# 2-RJ45.net
KiCad netlist of a schematic drawn in Altium Designer
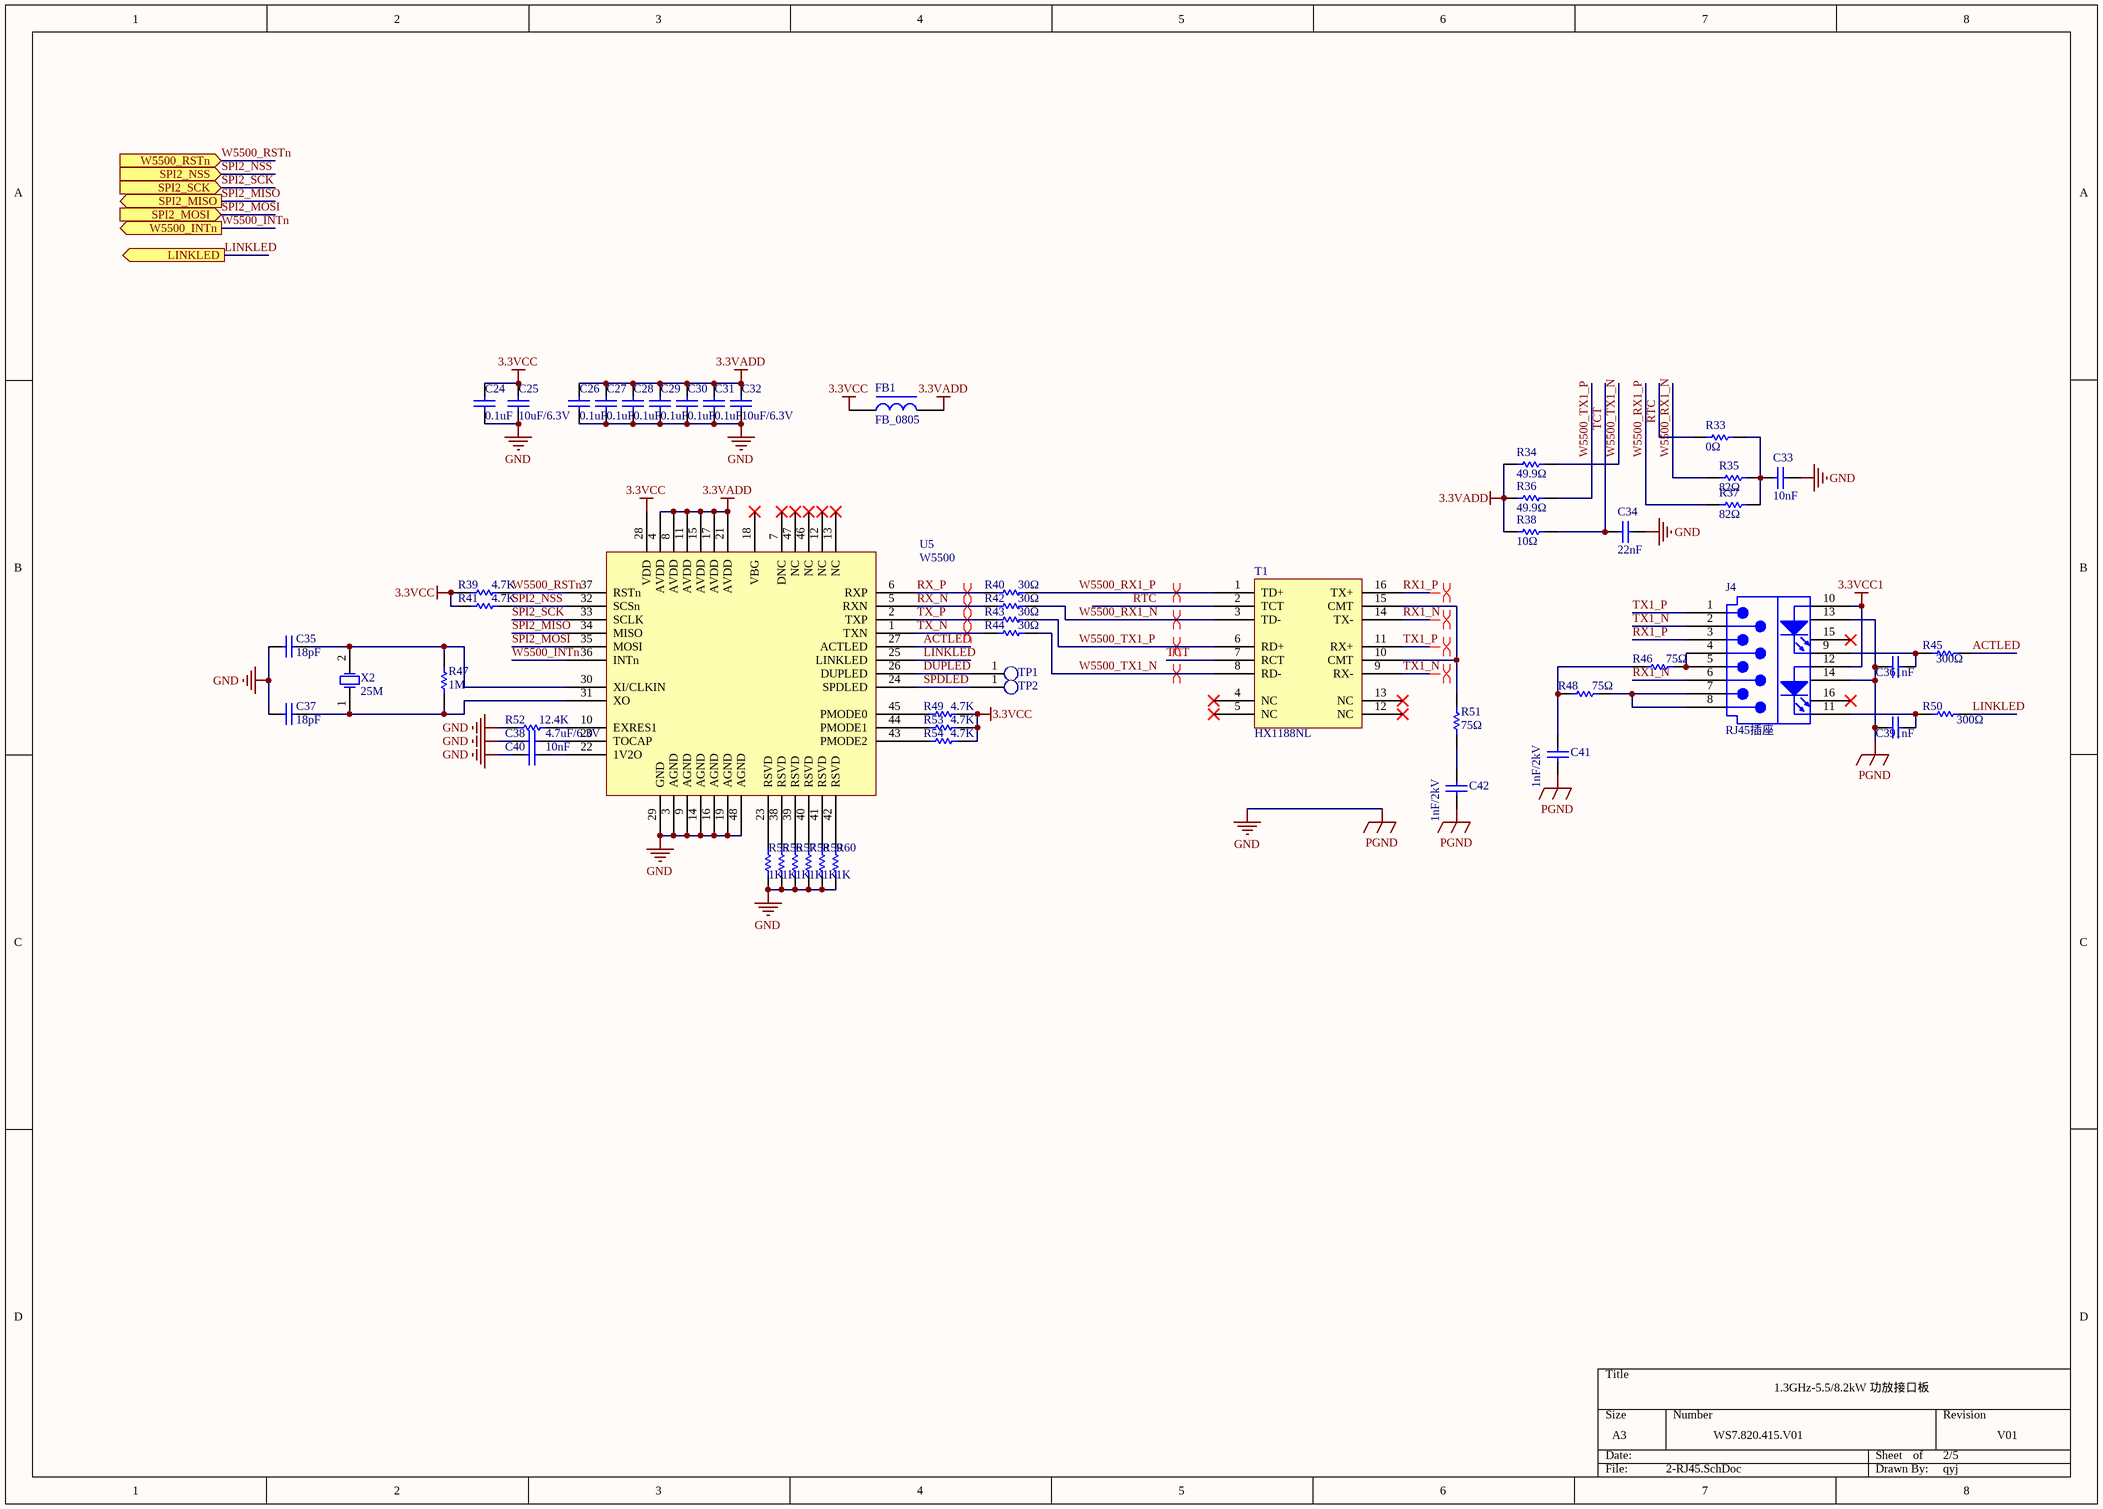
[diagram p0: 2-RJ45.SchDoc]

(export (version "E")
  (design (tool "Eeschema 10.0.6"))
  (components
    (comp (ref "C24")
      (value "0.1uF")
      (footprint "C0603")
      (description "贴片电容_GRM188R71H104KA01D_0.1uF±10%,50V,0603")
      (libsource (lib "20贴片电容0603") (part "0.1uF贴片电容"))
    )
    (comp (ref "C25")
      (value "10uF/6.3V")
      (footprint "C0603")
      (description "贴片电容_GRM188R60J106ME47D_10uF±20%,6.3V,0603")
      (libsource (lib "20贴片电容0603") (part "10uF贴片电容"))
    )
    (comp (ref "C26")
      (value "0.1uF")
      (footprint "C0603")
      (description "贴片电容_GRM188R71H104KA01D_0.1uF±10%,50V,0603")
      (libsource (lib "20贴片电容0603") (part "0.1uF贴片电容"))
    )
    (comp (ref "C27")
      (value "0.1uF")
      (footprint "C0603")
      (description "贴片电容_GRM188R71H104KA01D_0.1uF±10%,50V,0603")
      (libsource (lib "20贴片电容0603") (part "0.1uF贴片电容"))
    )
    (comp (ref "C28")
      (value "0.1uF")
      (footprint "C0603")
      (description "贴片电容_GRM188R71H104KA01D_0.1uF±10%,50V,0603")
      (libsource (lib "20贴片电容0603") (part "0.1uF贴片电容"))
    )
    (comp (ref "C29")
      (value "0.1uF")
      (footprint "C0603")
      (description "贴片电容_GRM188R71H104KA01D_0.1uF±10%,50V,0603")
      (libsource (lib "20贴片电容0603") (part "0.1uF贴片电容"))
    )
    (comp (ref "C30")
      (value "0.1uF")
      (footprint "C0603")
      (description "贴片电容_GRM188R71H104KA01D_0.1uF±10%,50V,0603")
      (libsource (lib "20贴片电容0603") (part "0.1uF贴片电容"))
    )
    (comp (ref "C31")
      (value "0.1uF")
      (footprint "C0603")
      (description "贴片电容_GRM188R71H104KA01D_0.1uF±10%,50V,0603")
      (libsource (lib "20贴片电容0603") (part "0.1uF贴片电容"))
    )
    (comp (ref "C32")
      (value "10uF/6.3V")
      (footprint "C0603")
      (description "贴片电容_GRM188R60J106ME47D_10uF±20%,6.3V,0603")
      (libsource (lib "20贴片电容0603") (part "10uF贴片电容"))
    )
    (comp (ref "C33")
      (value "10nF")
      (footprint "C0603")
      (description "C0603C103K5RAC_10nF±10%,50V,0603")
      (fields (field (name "MPN") "KEMET"))
      (libsource (lib "20贴片电容0603") (part "0.1uF贴片电容"))
    )
    (comp (ref "C34")
      (value "22nF")
      (footprint "C0603")
      (description "贴片电容_22nF±5%,50V,0603")
      (libsource (lib "20贴片电容0603") (part "27nF贴片电容"))
    )
    (comp (ref "C35")
      (value "18pF")
      (footprint "C0603")
      (description "贴片电容_GRM1885C1H180JA01D_18pF±5%,50V,0603")
      (libsource (lib "20贴片电容0603") (part "18pF贴片电容"))
    )
    (comp (ref "C36")
      (value "1nF")
      (footprint "C0603")
      (description "贴片电容_GRM188R71H102KA01_1000pF±10%,50V,0603")
      (libsource (lib "20贴片电容0603") (part "1000pF贴片电容"))
    )
    (comp (ref "C37")
      (value "18pF")
      (footprint "C0603")
      (description "贴片电容_GRM1885C1H180JA01D_18pF±5%,50V,0603")
      (libsource (lib "20贴片电容0603") (part "18pF贴片电容"))
    )
    (comp (ref "C38")
      (value "4.7uF/6.3V")
      (footprint "C0603")
      (description "GRM188R61C475K_4.7uF±10%,16V,0603")
      (fields (field (name "MPN") "Murata"))
      (libsource (lib "20贴片电容0603") (part "1uF贴片电容"))
    )
    (comp (ref "C39")
      (value "1nF")
      (footprint "C0603")
      (description "贴片电容_GRM188R71H102KA01_1000pF±10%,50V,0603")
      (libsource (lib "20贴片电容0603") (part "1000pF贴片电容"))
    )
    (comp (ref "C40")
      (value "10nF")
      (footprint "C0603")
      (description "C0603C103K5RAC_10nF±10%,50V,0603")
      (fields (field (name "MPN") "KEMET"))
      (libsource (lib "20贴片电容0603") (part "0.1uF贴片电容"))
    )
    (comp (ref "C41")
      (value "1nF/2kV")
      (footprint "C1206")
      (description "贴片电容_C1206C102J5GAC _1000pF±5%,50V,1206")
      (fields (field (name "MPN") "KEMET"))
      (libsource (lib "22贴片电容1210") (part "10uF贴片电容"))
    )
    (comp (ref "C42")
      (value "1nF/2kV")
      (footprint "C1206")
      (description "贴片电容_C1206C102J5GAC _1000pF±5%,50V,1206")
      (fields (field (name "MPN") "KEMET"))
      (libsource (lib "22贴片电容1210") (part "10uF贴片电容"))
    )
    (comp (ref "FB1")
      (value "FB_0805")
      (footprint "L0805")
      (description "贴片磁珠_600R,0805")
      (libsource (lib "32贴片磁珠0805") (part "0805贴片磁珠"))
    )
    (comp (ref "J4")
      (value "RJ45插座")
      (footprint "RJ45TH-1x1-2R54-LED")
      (description "RJ45插座_1*1,带左黄右绿灯,弯脚")
      (fields (field (name "MPN") "朱迅"))
      (libsource (lib "91连接器") (part "RJ45弯脚带灯"))
    )
    (comp (ref "R33")
      (value "0Ω")
      (footprint "R0603")
      (description "贴片电阻_0Ω±5%,0603")
      (libsource (lib "10贴片电阻0603") (part "0Ω贴片电阻"))
    )
    (comp (ref "R34")
      (value "49.9Ω")
      (footprint "R0603")
      (description "贴片电阻_49.9Ω±1%,0603")
      (libsource (lib "10贴片电阻0603") (part "51Ω贴片电阻"))
    )
    (comp (ref "R35")
      (value "82Ω")
      (footprint "R0603")
      (description "贴片电阻_82Ω±1%,0603")
      (libsource (lib "10贴片电阻0603") (part "51Ω贴片电阻"))
    )
    (comp (ref "R36")
      (value "49.9Ω")
      (footprint "R0603")
      (description "贴片电阻_49.9Ω±1%,0603")
      (libsource (lib "10贴片电阻0603") (part "51Ω贴片电阻"))
    )
    (comp (ref "R37")
      (value "82Ω")
      (footprint "R0603")
      (description "贴片电阻_82Ω±1%,0603")
      (libsource (lib "10贴片电阻0603") (part "51Ω贴片电阻"))
    )
    (comp (ref "R38")
      (value "10Ω")
      (footprint "R0603")
      (description "贴片电阻_10Ω±5%,0603")
      (libsource (lib "10贴片电阻0603") (part "10Ω贴片电阻"))
    )
    (comp (ref "R39")
      (value "4.7K")
      (footprint "R0603")
      (description "贴片电阻_4.7K±5%,0603")
      (libsource (lib "10贴片电阻0603") (part "4.7K贴片电阻"))
    )
    (comp (ref "R40")
      (value "30Ω")
      (footprint "R0603")
      (description "贴片电阻_30Ω±5%,0603")
      (libsource (lib "10贴片电阻0603") (part "30Ω贴片电阻"))
    )
    (comp (ref "R41")
      (value "4.7K")
      (footprint "R0603")
      (description "贴片电阻_4.7K±5%,0603")
      (libsource (lib "10贴片电阻0603") (part "4.7K贴片电阻"))
    )
    (comp (ref "R42")
      (value "30Ω")
      (footprint "R0603")
      (description "贴片电阻_30Ω±5%,0603")
      (libsource (lib "10贴片电阻0603") (part "30Ω贴片电阻"))
    )
    (comp (ref "R43")
      (value "30Ω")
      (footprint "R0603")
      (description "贴片电阻_30Ω±5%,0603")
      (libsource (lib "10贴片电阻0603") (part "30Ω贴片电阻"))
    )
    (comp (ref "R44")
      (value "30Ω")
      (footprint "R0603")
      (description "贴片电阻_30Ω±5%,0603")
      (libsource (lib "10贴片电阻0603") (part "30Ω贴片电阻"))
    )
    (comp (ref "R45")
      (value "300Ω")
      (footprint "R0603")
      (description "贴片电阻_300Ω±5%,0603")
      (libsource (lib "10贴片电阻0603") (part "300Ω贴片电阻"))
    )
    (comp (ref "R46")
      (value "75Ω")
      (footprint "R0805")
      (description "贴片电阻_75Ω±5%,0805")
      (libsource (lib "11贴片电阻0805") (part "75Ω贴片电阻"))
    )
    (comp (ref "R47")
      (value "1M")
      (footprint "R0603")
      (description "贴片电阻_1M±5%,0603")
      (libsource (lib "10贴片电阻0603") (part "1M贴片电阻"))
    )
    (comp (ref "R48")
      (value "75Ω")
      (footprint "R0805")
      (description "贴片电阻_75Ω±5%,0805")
      (libsource (lib "11贴片电阻0805") (part "75Ω贴片电阻"))
    )
    (comp (ref "R49")
      (value "4.7K")
      (footprint "R0603")
      (description "贴片电阻_4.7K±5%,0603")
      (libsource (lib "10贴片电阻0603") (part "4.7K贴片电阻"))
    )
    (comp (ref "R50")
      (value "300Ω")
      (footprint "R0603")
      (description "贴片电阻_300Ω±5%,0603")
      (libsource (lib "10贴片电阻0603") (part "300Ω贴片电阻"))
    )
    (comp (ref "R51")
      (value "75Ω")
      (footprint "R1206")
      (description "贴片电阻_75Ω±5%,1206")
      (libsource (lib "11贴片电阻0805") (part "75Ω贴片电阻"))
    )
    (comp (ref "R52")
      (value "12.4K")
      (footprint "R0603")
      (description "贴片电阻_12.4K±1%,0603")
      (libsource (lib "10贴片电阻0603") (part "12K贴片电阻"))
    )
    (comp (ref "R53")
      (value "4.7K")
      (footprint "R0603")
      (description "贴片电阻_4.7K±5%,0603")
      (libsource (lib "10贴片电阻0603") (part "4.7K贴片电阻"))
    )
    (comp (ref "R54")
      (value "4.7K")
      (footprint "R0603")
      (description "贴片电阻_4.7K±5%,0603")
      (libsource (lib "10贴片电阻0603") (part "4.7K贴片电阻"))
    )
    (comp (ref "R55")
      (value "1K")
      (footprint "R0603")
      (description "贴片电阻_1K±5%,0603")
      (libsource (lib "10贴片电阻0603") (part "1K贴片电阻"))
    )
    (comp (ref "R56")
      (value "1K")
      (footprint "R0603")
      (description "贴片电阻_1K±5%,0603")
      (libsource (lib "10贴片电阻0603") (part "1K贴片电阻"))
    )
    (comp (ref "R57")
      (value "1K")
      (footprint "R0603")
      (description "贴片电阻_1K±5%,0603")
      (libsource (lib "10贴片电阻0603") (part "1K贴片电阻"))
    )
    (comp (ref "R58")
      (value "1K")
      (footprint "R0603")
      (description "贴片电阻_1K±5%,0603")
      (libsource (lib "10贴片电阻0603") (part "1K贴片电阻"))
    )
    (comp (ref "R59")
      (value "1K")
      (footprint "R0603")
      (description "贴片电阻_1K±5%,0603")
      (libsource (lib "10贴片电阻0603") (part "1K贴片电阻"))
    )
    (comp (ref "R60")
      (value "1K")
      (footprint "R0603")
      (description "贴片电阻_1K±5%,0603")
      (libsource (lib "10贴片电阻0603") (part "1K贴片电阻"))
    )
    (comp (ref "T1")
      (value "HX1188NL")
      (footprint "SOP16-1R27-7R11x12R7")
      (description "网络变压器_HX1188NL_百兆,SOIC16")
      (libsource (lib "89网络变压器") (part "HX1188NL"))
    )
    (comp (ref "TP1")
      (value "TEST")
      (footprint "TP0R8")
      (description "表贴测试点0.8mm")
      (libsource (lib "103其他（hole，test等）") (part "TP0.8mm"))
    )
    (comp (ref "TP2")
      (value "TEST")
      (footprint "TP0R8")
      (description "表贴测试点0.8mm")
      (libsource (lib "103其他（hole，test等）") (part "TP0.8mm"))
    )
    (comp (ref "U5")
      (value "W5500")
      (footprint "TQFN48-0R5-7X7")
      (description "以太网控制器_W5500_LQFP48")
      (libsource (lib "86网口芯片") (part "W5500"))
    )
    (comp (ref "X2")
      (value "25M")
      (footprint "CRY2SM-6R0x3R5")
      (description "贴片无源晶体_25MHz,30ppm,6035封装")
      (libsource (lib "60振荡器") (part "25M贴片无源晶体"))
    )
  )
  (nets
    (net (code "1") (name "/ACTLED") (class "Default")
      (node (ref "R45") (pin "2") (pinfunction "2_2") (pintype "passive"))
      (node (ref "U5") (pin "27") (pinfunction "ACTLED_27") (pintype "passive"))
    )
    (net (code "2") (name "/DUPLED") (class "Default")
      (node (ref "TP1") (pin "1") (pinfunction "TP_1") (pintype "passive"))
      (node (ref "U5") (pin "26") (pinfunction "DUPLED_26") (pintype "passive"))
    )
    (net (code "3") (name "/LINKLED") (class "Default")
      (node (ref "R50") (pin "2") (pinfunction "2_2") (pintype "passive"))
      (node (ref "U5") (pin "25") (pinfunction "LINKLED_25") (pintype "passive"))
    )
    (net (code "4") (name "/RTC") (class "Default")
      (node (ref "R33") (pin "2") (pinfunction "2_2") (pintype "passive"))
      (node (ref "T1") (pin "2") (pinfunction "TCT_2") (pintype "passive"))
    )
    (net (code "5") (name "/RX1_N") (class "Default")
      (node (ref "J4") (pin "6") (pinfunction "RX-_6") (pintype "passive"))
      (node (ref "T1") (pin "14") (pinfunction "TX-_14") (pintype "passive"))
    )
    (net (code "6") (name "/RX1_P") (class "Default")
      (node (ref "J4") (pin "3") (pinfunction "RX+_3") (pintype "passive"))
      (node (ref "T1") (pin "16") (pinfunction "TX+_16") (pintype "passive"))
    )
    (net (code "7") (name "/RX_N") (class "Default")
      (node (ref "R42") (pin "1") (pinfunction "1_1") (pintype "passive"))
      (node (ref "U5") (pin "5") (pinfunction "RXN_5") (pintype "passive"))
    )
    (net (code "8") (name "/RX_P") (class "Default")
      (node (ref "R40") (pin "1") (pinfunction "1_1") (pintype "passive"))
      (node (ref "U5") (pin "6") (pinfunction "RXP_6") (pintype "passive"))
    )
    (net (code "9") (name "/SPDLED") (class "Default")
      (node (ref "TP2") (pin "1") (pinfunction "TP_1") (pintype "passive"))
      (node (ref "U5") (pin "24") (pinfunction "SPDLED_24") (pintype "passive"))
    )
    (net (code "10") (name "/SPI2_MISO") (class "Default")
      (node (ref "U5") (pin "34") (pinfunction "MISO_34") (pintype "passive"))
    )
    (net (code "11") (name "/SPI2_MOSI") (class "Default")
      (node (ref "U5") (pin "35") (pinfunction "MOSI_35") (pintype "passive"))
    )
    (net (code "12") (name "/SPI2_NSS") (class "Default")
      (node (ref "R41") (pin "1") (pinfunction "1_1") (pintype "passive"))
      (node (ref "U5") (pin "32") (pinfunction "SCSn_32") (pintype "passive"))
    )
    (net (code "13") (name "/SPI2_SCK") (class "Default")
      (node (ref "U5") (pin "33") (pinfunction "SCLK_33") (pintype "passive"))
    )
    (net (code "14") (name "/TCT") (class "Default")
      (node (ref "C34") (pin "2") (pinfunction "2_2") (pintype "passive"))
      (node (ref "R38") (pin "1") (pinfunction "1_1") (pintype "passive"))
      (node (ref "T1") (pin "7") (pinfunction "RCT_7") (pintype "passive"))
    )
    (net (code "15") (name "/TX1_N") (class "Default")
      (node (ref "J4") (pin "2") (pinfunction "TX-_2") (pintype "passive"))
      (node (ref "T1") (pin "9") (pinfunction "RX-_9") (pintype "passive"))
    )
    (net (code "16") (name "/TX1_P") (class "Default")
      (node (ref "J4") (pin "1") (pinfunction "TX+_1") (pintype "passive"))
      (node (ref "T1") (pin "11") (pinfunction "RX+_11") (pintype "passive"))
    )
    (net (code "17") (name "/TX_N") (class "Default")
      (node (ref "R44") (pin "1") (pinfunction "1_1") (pintype "passive"))
      (node (ref "U5") (pin "1") (pinfunction "TXN_1") (pintype "passive"))
    )
    (net (code "18") (name "/TX_P") (class "Default")
      (node (ref "R43") (pin "1") (pinfunction "1_1") (pintype "passive"))
      (node (ref "U5") (pin "2") (pinfunction "TXP_2") (pintype "passive"))
    )
    (net (code "19") (name "/W5500_INTn") (class "Default")
      (node (ref "U5") (pin "36") (pinfunction "INTn_36") (pintype "passive"))
    )
    (net (code "20") (name "/W5500_RSTn") (class "Default")
      (node (ref "R39") (pin "1") (pinfunction "1_1") (pintype "passive"))
      (node (ref "U5") (pin "37") (pinfunction "RSTn_37") (pintype "passive"))
    )
    (net (code "21") (name "/W5500_RX1_N") (class "Default")
      (node (ref "R35") (pin "2") (pinfunction "2_2") (pintype "passive"))
      (node (ref "R42") (pin "2") (pinfunction "2_2") (pintype "passive"))
      (node (ref "T1") (pin "3") (pinfunction "TD-_3") (pintype "passive"))
    )
    (net (code "22") (name "/W5500_RX1_P") (class "Default")
      (node (ref "R37") (pin "2") (pinfunction "2_2") (pintype "passive"))
      (node (ref "R40") (pin "2") (pinfunction "2_2") (pintype "passive"))
      (node (ref "T1") (pin "1") (pinfunction "TD+_1") (pintype "passive"))
    )
    (net (code "23") (name "/W5500_TX1_N") (class "Default")
      (node (ref "R34") (pin "1") (pinfunction "1_1") (pintype "passive"))
      (node (ref "R44") (pin "2") (pinfunction "2_2") (pintype "passive"))
      (node (ref "T1") (pin "8") (pinfunction "RD-_8") (pintype "passive"))
    )
    (net (code "24") (name "/W5500_TX1_P") (class "Default")
      (node (ref "R36") (pin "1") (pinfunction "1_1") (pintype "passive"))
      (node (ref "R43") (pin "2") (pinfunction "2_2") (pintype "passive"))
      (node (ref "T1") (pin "6") (pinfunction "RD+_6") (pintype "passive"))
    )
    (net (code "25") (name "3.3VADD") (class "Default")
      (node (ref "C26") (pin "2") (pinfunction "2_2") (pintype "passive"))
      (node (ref "C27") (pin "2") (pinfunction "2_2") (pintype "passive"))
      (node (ref "C28") (pin "2") (pinfunction "2_2") (pintype "passive"))
      (node (ref "C29") (pin "2") (pinfunction "2_2") (pintype "passive"))
      (node (ref "C30") (pin "2") (pinfunction "2_2") (pintype "passive"))
      (node (ref "C31") (pin "2") (pinfunction "2_2") (pintype "passive"))
      (node (ref "C32") (pin "2") (pinfunction "2_2") (pintype "passive"))
      (node (ref "FB1") (pin "2") (pinfunction "2_2") (pintype "passive"))
      (node (ref "R34") (pin "2") (pinfunction "2_2") (pintype "passive"))
      (node (ref "R36") (pin "2") (pinfunction "2_2") (pintype "passive"))
      (node (ref "R38") (pin "2") (pinfunction "2_2") (pintype "passive"))
      (node (ref "U5") (pin "11") (pinfunction "AVDD_11") (pintype "passive"))
      (node (ref "U5") (pin "15") (pinfunction "AVDD_15") (pintype "passive"))
      (node (ref "U5") (pin "17") (pinfunction "AVDD_17") (pintype "passive"))
      (node (ref "U5") (pin "21") (pinfunction "AVDD_21") (pintype "passive"))
      (node (ref "U5") (pin "4") (pinfunction "AVDD_4") (pintype "passive"))
      (node (ref "U5") (pin "8") (pinfunction "AVDD_8") (pintype "passive"))
    )
    (net (code "26") (name "3.3VCC") (class "Default")
      (node (ref "C24") (pin "2") (pinfunction "2_2") (pintype "passive"))
      (node (ref "C25") (pin "2") (pinfunction "2_2") (pintype "passive"))
      (node (ref "FB1") (pin "1") (pinfunction "1_1") (pintype "passive"))
      (node (ref "R39") (pin "2") (pinfunction "2_2") (pintype "passive"))
      (node (ref "R41") (pin "2") (pinfunction "2_2") (pintype "passive"))
      (node (ref "R49") (pin "2") (pinfunction "2_2") (pintype "passive"))
      (node (ref "R53") (pin "2") (pinfunction "2_2") (pintype "passive"))
      (node (ref "R54") (pin "2") (pinfunction "2_2") (pintype "passive"))
      (node (ref "U5") (pin "28") (pinfunction "VDD_28") (pintype "passive"))
    )
    (net (code "27") (name "3.3VCC1") (class "Default")
      (node (ref "J4") (pin "10") (pinfunction "A1_10") (pintype "passive"))
      (node (ref "J4") (pin "12") (pinfunction "A2_12") (pintype "passive"))
    )
    (net (code "28") (name "GND") (class "Default")
      (node (ref "C24") (pin "1") (pinfunction "1_1") (pintype "passive"))
      (node (ref "C25") (pin "1") (pinfunction "1_1") (pintype "passive"))
      (node (ref "C26") (pin "1") (pinfunction "1_1") (pintype "passive"))
      (node (ref "C27") (pin "1") (pinfunction "1_1") (pintype "passive"))
      (node (ref "C28") (pin "1") (pinfunction "1_1") (pintype "passive"))
      (node (ref "C29") (pin "1") (pinfunction "1_1") (pintype "passive"))
      (node (ref "C30") (pin "1") (pinfunction "1_1") (pintype "passive"))
      (node (ref "C31") (pin "1") (pinfunction "1_1") (pintype "passive"))
      (node (ref "C32") (pin "1") (pinfunction "1_1") (pintype "passive"))
      (node (ref "C33") (pin "1") (pinfunction "1_1") (pintype "passive"))
      (node (ref "C34") (pin "1") (pinfunction "1_1") (pintype "passive"))
      (node (ref "C35") (pin "1") (pinfunction "1_1") (pintype "passive"))
      (node (ref "C36") (pin "1") (pinfunction "1_1") (pintype "passive"))
      (node (ref "C37") (pin "1") (pinfunction "1_1") (pintype "passive"))
      (node (ref "C38") (pin "1") (pinfunction "1_1") (pintype "passive"))
      (node (ref "C39") (pin "1") (pinfunction "1_1") (pintype "passive"))
      (node (ref "C40") (pin "1") (pinfunction "1_1") (pintype "passive"))
      (node (ref "C41") (pin "1") (pinfunction "1_1") (pintype "passive"))
      (node (ref "C42") (pin "1") (pinfunction "1_1") (pintype "passive"))
      (node (ref "J4") (pin "13") (pinfunction "13_13") (pintype "passive"))
      (node (ref "J4") (pin "14") (pinfunction "14_14") (pintype "passive"))
      (node (ref "R52") (pin "1") (pinfunction "1_1") (pintype "passive"))
      (node (ref "R55") (pin "1") (pinfunction "1_1") (pintype "passive"))
      (node (ref "R56") (pin "1") (pinfunction "1_1") (pintype "passive"))
      (node (ref "R57") (pin "1") (pinfunction "1_1") (pintype "passive"))
      (node (ref "R58") (pin "1") (pinfunction "1_1") (pintype "passive"))
      (node (ref "R59") (pin "1") (pinfunction "1_1") (pintype "passive"))
      (node (ref "R60") (pin "1") (pinfunction "1_1") (pintype "passive"))
      (node (ref "U5") (pin "14") (pinfunction "AGND_14") (pintype "passive"))
      (node (ref "U5") (pin "16") (pinfunction "AGND_16") (pintype "passive"))
      (node (ref "U5") (pin "19") (pinfunction "AGND_19") (pintype "passive"))
      (node (ref "U5") (pin "29") (pinfunction "GND_29") (pintype "passive"))
      (node (ref "U5") (pin "3") (pinfunction "AGND_3") (pintype "passive"))
      (node (ref "U5") (pin "48") (pinfunction "AGND_48") (pintype "passive"))
      (node (ref "U5") (pin "9") (pinfunction "AGND_9") (pintype "passive"))
    )
    (net (code "29") (name "Net-(C33-Pad2)") (class "Default")
      (node (ref "C33") (pin "2") (pinfunction "2_2") (pintype "passive"))
      (node (ref "R33") (pin "1") (pinfunction "1_1") (pintype "passive"))
      (node (ref "R35") (pin "1") (pinfunction "1_1") (pintype "passive"))
      (node (ref "R37") (pin "1") (pinfunction "1_1") (pintype "passive"))
    )
    (net (code "30") (name "Net-(C41-Pad2)") (class "Default")
      (node (ref "C41") (pin "2") (pinfunction "2_2") (pintype "passive"))
      (node (ref "R46") (pin "1") (pinfunction "1_1") (pintype "passive"))
      (node (ref "R48") (pin "1") (pinfunction "1_1") (pintype "passive"))
    )
    (net (code "31") (name "Net-(C42-Pad2)") (class "Default")
      (node (ref "C42") (pin "2") (pinfunction "2_2") (pintype "passive"))
      (node (ref "R51") (pin "1") (pinfunction "1_1") (pintype "passive"))
    )
    (net (code "32") (name "Net-(J4-K1)") (class "Default")
      (node (ref "C36") (pin "2") (pinfunction "2_2") (pintype "passive"))
      (node (ref "J4") (pin "9") (pinfunction "K1_9") (pintype "passive"))
      (node (ref "R45") (pin "1") (pinfunction "1_1") (pintype "passive"))
    )
    (net (code "33") (name "Net-(J4-K2)") (class "Default")
      (node (ref "C39") (pin "2") (pinfunction "2_2") (pintype "passive"))
      (node (ref "J4") (pin "11") (pinfunction "K2_11") (pintype "passive"))
      (node (ref "R50") (pin "1") (pinfunction "1_1") (pintype "passive"))
    )
    (net (code "34") (name "Net-(J4-NC-Pad4)") (class "Default")
      (node (ref "J4") (pin "4") (pinfunction "NC_4") (pintype "passive"))
      (node (ref "J4") (pin "5") (pinfunction "NC_5") (pintype "passive"))
      (node (ref "R46") (pin "2") (pinfunction "2_2") (pintype "passive"))
    )
    (net (code "35") (name "Net-(J4-NC-Pad7)") (class "Default")
      (node (ref "J4") (pin "7") (pinfunction "NC_7") (pintype "passive"))
      (node (ref "J4") (pin "8") (pinfunction "NC_8") (pintype "passive"))
      (node (ref "R48") (pin "2") (pinfunction "2_2") (pintype "passive"))
    )
    (net (code "36") (name "Net-(R51-Pad2)") (class "Default")
      (node (ref "R51") (pin "2") (pinfunction "2_2") (pintype "passive"))
      (node (ref "T1") (pin "10") (pinfunction "CMT_10") (pintype "passive"))
      (node (ref "T1") (pin "15") (pinfunction "CMT_15") (pintype "passive"))
    )
    (net (code "37") (name "Net-(R55-Pad2)") (class "Default")
      (node (ref "R55") (pin "2") (pinfunction "2_2") (pintype "passive"))
      (node (ref "U5") (pin "23") (pinfunction "RSVD_23") (pintype "passive"))
    )
    (net (code "38") (name "Net-(R56-Pad2)") (class "Default")
      (node (ref "R56") (pin "2") (pinfunction "2_2") (pintype "passive"))
      (node (ref "U5") (pin "38") (pinfunction "RSVD_38") (pintype "passive"))
    )
    (net (code "39") (name "Net-(R57-Pad2)") (class "Default")
      (node (ref "R57") (pin "2") (pinfunction "2_2") (pintype "passive"))
      (node (ref "U5") (pin "39") (pinfunction "RSVD_39") (pintype "passive"))
    )
    (net (code "40") (name "Net-(R58-Pad2)") (class "Default")
      (node (ref "R58") (pin "2") (pinfunction "2_2") (pintype "passive"))
      (node (ref "U5") (pin "40") (pinfunction "RSVD_40") (pintype "passive"))
    )
    (net (code "41") (name "Net-(R59-Pad2)") (class "Default")
      (node (ref "R59") (pin "2") (pinfunction "2_2") (pintype "passive"))
      (node (ref "U5") (pin "41") (pinfunction "RSVD_41") (pintype "passive"))
    )
    (net (code "42") (name "Net-(R60-Pad2)") (class "Default")
      (node (ref "R60") (pin "2") (pinfunction "2_2") (pintype "passive"))
      (node (ref "U5") (pin "42") (pinfunction "RSVD_42") (pintype "passive"))
    )
    (net (code "43") (name "Net-(U5-1V2O)") (class "Default")
      (node (ref "C40") (pin "2") (pinfunction "2_2") (pintype "passive"))
      (node (ref "U5") (pin "22") (pinfunction "1V2O_22") (pintype "passive"))
    )
    (net (code "44") (name "Net-(U5-EXRES1)") (class "Default")
      (node (ref "R52") (pin "2") (pinfunction "2_2") (pintype "passive"))
      (node (ref "U5") (pin "10") (pinfunction "EXRES1_10") (pintype "passive"))
    )
    (net (code "45") (name "Net-(U5-PMODE0)") (class "Default")
      (node (ref "R49") (pin "1") (pinfunction "1_1") (pintype "passive"))
      (node (ref "U5") (pin "45") (pinfunction "PMODE0_45") (pintype "passive"))
    )
    (net (code "46") (name "Net-(U5-PMODE1)") (class "Default")
      (node (ref "R53") (pin "1") (pinfunction "1_1") (pintype "passive"))
      (node (ref "U5") (pin "44") (pinfunction "PMODE1_44") (pintype "passive"))
    )
    (net (code "47") (name "Net-(U5-PMODE2)") (class "Default")
      (node (ref "R54") (pin "1") (pinfunction "1_1") (pintype "passive"))
      (node (ref "U5") (pin "43") (pinfunction "PMODE2_43") (pintype "passive"))
    )
    (net (code "48") (name "Net-(U5-TOCAP)") (class "Default")
      (node (ref "C38") (pin "2") (pinfunction "2_2") (pintype "passive"))
      (node (ref "U5") (pin "20") (pinfunction "TOCAP_20") (pintype "passive"))
    )
    (net (code "49") (name "Net-(U5-XI{slash}CLKIN)") (class "Default")
      (node (ref "C35") (pin "2") (pinfunction "2_2") (pintype "passive"))
      (node (ref "R47") (pin "2") (pinfunction "2_2") (pintype "passive"))
      (node (ref "U5") (pin "30") (pinfunction "XI/CLKIN_30") (pintype "passive"))
      (node (ref "X2") (pin "2") (pinfunction "OSC2_2") (pintype "passive"))
    )
    (net (code "50") (name "Net-(U5-XO)") (class "Default")
      (node (ref "C37") (pin "2") (pinfunction "2_2") (pintype "passive"))
      (node (ref "R47") (pin "1") (pinfunction "1_1") (pintype "passive"))
      (node (ref "U5") (pin "31") (pinfunction "XO_31") (pintype "passive"))
      (node (ref "X2") (pin "1") (pinfunction "OSC1_1") (pintype "passive"))
    )
    (net (code "51") (name "unconnected-(J4-Pad15)") (class "Default")
      (node (ref "J4") (pin "15") (pinfunction "15_15") (pintype "passive+no_connect"))
    )
    (net (code "52") (name "unconnected-(J4-Pad16)") (class "Default")
      (node (ref "J4") (pin "16") (pinfunction "16_16") (pintype "passive+no_connect"))
    )
    (net (code "53") (name "unconnected-(T1-NC-Pad4)") (class "Default")
      (node (ref "T1") (pin "4") (pinfunction "NC_4") (pintype "passive+no_connect"))
    )
    (net (code "54") (name "unconnected-(T1-NC-Pad5)") (class "Default")
      (node (ref "T1") (pin "5") (pinfunction "NC_5") (pintype "passive+no_connect"))
    )
    (net (code "55") (name "unconnected-(T1-NC-Pad12)") (class "Default")
      (node (ref "T1") (pin "12") (pinfunction "NC_12") (pintype "passive+no_connect"))
    )
    (net (code "56") (name "unconnected-(T1-NC-Pad13)") (class "Default")
      (node (ref "T1") (pin "13") (pinfunction "NC_13") (pintype "passive+no_connect"))
    )
    (net (code "57") (name "unconnected-(U5-DNC-Pad7)") (class "Default")
      (node (ref "U5") (pin "7") (pinfunction "DNC_7") (pintype "passive+no_connect"))
    )
    (net (code "58") (name "unconnected-(U5-NC-Pad12)") (class "Default")
      (node (ref "U5") (pin "12") (pinfunction "NC_12") (pintype "passive+no_connect"))
    )
    (net (code "59") (name "unconnected-(U5-NC-Pad13)") (class "Default")
      (node (ref "U5") (pin "13") (pinfunction "NC_13") (pintype "passive+no_connect"))
    )
    (net (code "60") (name "unconnected-(U5-NC-Pad46)") (class "Default")
      (node (ref "U5") (pin "46") (pinfunction "NC_46") (pintype "passive+no_connect"))
    )
    (net (code "61") (name "unconnected-(U5-NC-Pad47)") (class "Default")
      (node (ref "U5") (pin "47") (pinfunction "NC_47") (pintype "passive+no_connect"))
    )
    (net (code "62") (name "unconnected-(U5-VBG-Pad18)") (class "Default")
      (node (ref "U5") (pin "18") (pinfunction "VBG_18") (pintype "passive+no_connect"))
    )
  )
)
